# SyncLED.net
KiCad netlist of a schematic drawn in EAGLE
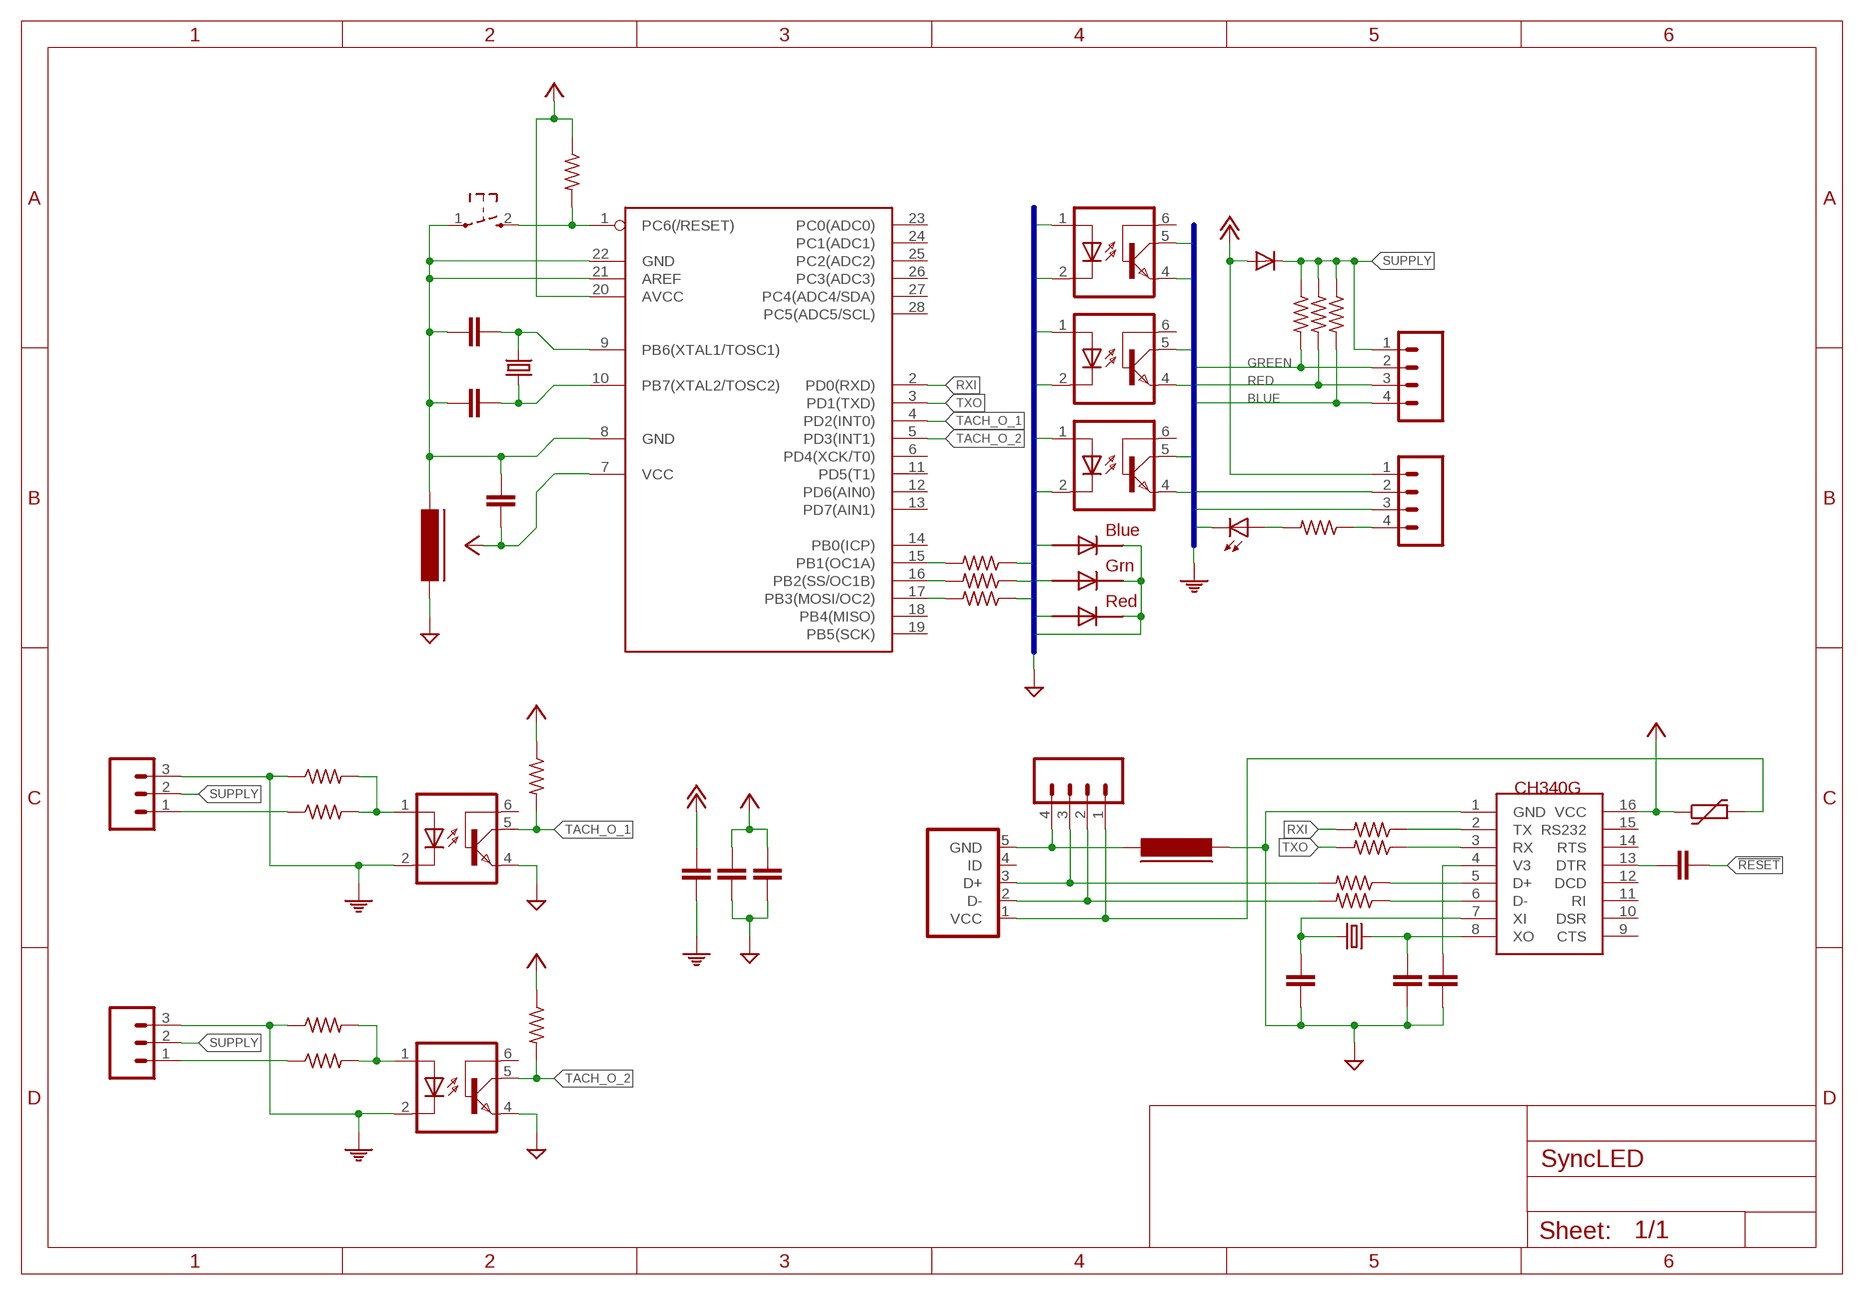
[diagram p0: schematic, sheet 1]

(export (version "E")
  (design (tool "Eeschema 10.0.6"))
  (components
    (comp (ref "!RES")
      (value "SMD")
      (footprint "eagle-import:SW_TACT_3X6")
      (libsource (lib "eagle-import") (part "SW_TACT_2P-3X6"))
    )
    (comp (ref "C1")
      (value "22pF")
      (footprint "eagle-import:C0805K")
      (libsource (lib "eagle-import") (part "C-EUC0805K"))
    )
    (comp (ref "C2")
      (value "22pF")
      (footprint "eagle-import:C0805K")
      (libsource (lib "eagle-import") (part "C-EUC0805K"))
    )
    (comp (ref "C3")
      (value "22pF")
      (footprint "eagle-import:C0805K")
      (libsource (lib "eagle-import") (part "C-EUC0805K"))
    )
    (comp (ref "C4")
      (value "22pF")
      (footprint "eagle-import:C0805K")
      (libsource (lib "eagle-import") (part "C-EUC0805K"))
    )
    (comp (ref "CAP_!DTR")
      (value "100nF")
      (footprint "eagle-import:C1206K")
      (libsource (lib "eagle-import") (part "C-EUC1206K"))
    )
    (comp (ref "CAP_BYPASS")
      (value "22pF")
      (footprint "eagle-import:C0805K")
      (libsource (lib "eagle-import") (part "C-EUC0805K"))
    )
    (comp (ref "CAP_DIGITAL_1")
      (value "1uF")
      (footprint "eagle-import:C1210K")
      (libsource (lib "eagle-import") (part "C-EUC1210K"))
    )
    (comp (ref "CAP_DIGITAL_2")
      (value "1uF")
      (footprint "eagle-import:C1210K")
      (libsource (lib "eagle-import") (part "C-EUC1210K"))
    )
    (comp (ref "CAP_LED")
      (value "1uF")
      (footprint "eagle-import:C1206K")
      (libsource (lib "eagle-import") (part "C-EUC1206K"))
    )
    (comp (ref "CAP_MCU")
      (value "10uF")
      (footprint "eagle-import:C1206K")
      (libsource (lib "eagle-import") (part "C-EUC1206K"))
    )
    (comp (ref "DIODE_LED")
      (value "1N4004")
      (footprint "eagle-import:DO41-10")
      (libsource (lib "eagle-import") (part "1N4004"))
    )
    (comp (ref "FAN_HEADER_1")
      (value "M03PTH")
      (footprint "eagle-import:1X03")
      (libsource (lib "eagle-import") (part "M03PTH"))
    )
    (comp (ref "FAN_HEADER_2")
      (value "M03PTH")
      (footprint "eagle-import:1X03")
      (libsource (lib "eagle-import") (part "M03PTH"))
    )
    (comp (ref "FERRITE_MCU")
      (value "UGND")
      (footprint "eagle-import:FB805")
      (libsource (lib "eagle-import") (part "FERRITE-0805"))
    )
    (comp (ref "FERRITE_USB")
      (value "UGND")
      (footprint "eagle-import:FB805")
      (libsource (lib "eagle-import") (part "FERRITE-0805"))
    )
    (comp (ref "INDICATOR")
      (value "RGBLED5050")
      (footprint "eagle-import:RGBLED5050")
      (libsource (lib "eagle-import") (part "RGBLED5050"))
    )
    (comp (ref "LED_OUTPUT")
      (value "M04PTH")
      (footprint "eagle-import:1X04")
      (libsource (lib "eagle-import") (part "SparkFun-Connectors_M04PTH"))
    )
    (comp (ref "MCU")
      (value "MEGA8-P")
      (footprint "eagle-import:DIL28-3")
      (libsource (lib "eagle-import") (part "MEGA8-P"))
    )
    (comp (ref "OPTO_BLUE")
      (value "4N35")
      (footprint "eagle-import:DIL06")
      (fields (field (name "MF") "FAIRCHILD SEMICONDUCTOR"))
      (libsource (lib "eagle-import") (part "4N35"))
    )
    (comp (ref "OPTO_GREEN")
      (value "4N35")
      (footprint "eagle-import:DIL06")
      (fields (field (name "MF") "FAIRCHILD SEMICONDUCTOR"))
      (libsource (lib "eagle-import") (part "4N35"))
    )
    (comp (ref "OPTO_RED")
      (value "4N35")
      (footprint "eagle-import:DIL06")
      (fields (field (name "MF") "FAIRCHILD SEMICONDUCTOR"))
      (libsource (lib "eagle-import") (part "4N35"))
    )
    (comp (ref "OPTO_TACH_1")
      (value "4N35")
      (footprint "eagle-import:DIL06")
      (fields (field (name "MF") "FAIRCHILD SEMICONDUCTOR"))
      (libsource (lib "eagle-import") (part "4N35"))
    )
    (comp (ref "OPTO_TACH_2")
      (value "4N35")
      (footprint "eagle-import:DIL06")
      (fields (field (name "MF") "FAIRCHILD SEMICONDUCTOR"))
      (libsource (lib "eagle-import") (part "4N35"))
    )
    (comp (ref "POWER_INDICATOR")
      (value "LEDCHIPLED_1206")
      (footprint "eagle-import:CHIPLED_1206")
      (libsource (lib "eagle-import") (part "LEDCHIPLED_1206"))
    )
    (comp (ref "PPTC")
      (value "500mA")
      (footprint "eagle-import:PTC0805")
      (libsource (lib "eagle-import") (part "FUSE_PTC-0805"))
    )
    (comp (ref "RES_BLUE")
      (value "10K")
      (footprint "eagle-import:0207_10")
      (libsource (lib "eagle-import") (part "R-US_0207/10"))
    )
    (comp (ref "RES_B_IN")
      (value "100E")
      (footprint "eagle-import:0207_12")
      (libsource (lib "eagle-import") (part "R-US_0207/12"))
    )
    (comp (ref "RES_D+")
      (value "100E")
      (footprint "eagle-import:M0805")
      (libsource (lib "eagle-import") (part "R-US_M0805"))
    )
    (comp (ref "RES_D-")
      (value "100E")
      (footprint "eagle-import:M0805")
      (libsource (lib "eagle-import") (part "R-US_M0805"))
    )
    (comp (ref "RES_GREEN")
      (value "10K")
      (footprint "eagle-import:0207_10")
      (libsource (lib "eagle-import") (part "R-US_0207/10"))
    )
    (comp (ref "RES_G_IN")
      (value "100E")
      (footprint "eagle-import:0207_12")
      (libsource (lib "eagle-import") (part "R-US_0207/12"))
    )
    (comp (ref "RES_LED")
      (value "10K")
      (footprint "eagle-import:M1206")
      (libsource (lib "eagle-import") (part "R-US_M1206"))
    )
    (comp (ref "RES_PULLUP")
      (value "10K")
      (footprint "eagle-import:0207_12")
      (libsource (lib "eagle-import") (part "R-US_0207/12"))
    )
    (comp (ref "RES_RED")
      (value "10K")
      (footprint "eagle-import:0207_10")
      (libsource (lib "eagle-import") (part "R-US_0207/10"))
    )
    (comp (ref "RES_RX")
      (value "100E")
      (footprint "eagle-import:0207_10")
      (libsource (lib "eagle-import") (part "R-US_0207/10"))
    )
    (comp (ref "RES_R_IN")
      (value "100E")
      (footprint "eagle-import:0207_12")
      (libsource (lib "eagle-import") (part "R-US_0207/12"))
    )
    (comp (ref "RES_TACH_1")
      (value "100E")
      (footprint "eagle-import:0207_10")
      (libsource (lib "eagle-import") (part "R-US_0207/10"))
    )
    (comp (ref "RES_TACH_2")
      (value "100E")
      (footprint "eagle-import:0207_10")
      (libsource (lib "eagle-import") (part "R-US_0207/10"))
    )
    (comp (ref "RES_TACH_PULLDOWN_1")
      (value "1K")
      (footprint "eagle-import:0207_10")
      (libsource (lib "eagle-import") (part "R-US_0207/10"))
    )
    (comp (ref "RES_TACH_PULLDOWN_2")
      (value "1K")
      (footprint "eagle-import:0207_10")
      (libsource (lib "eagle-import") (part "R-US_0207/10"))
    )
    (comp (ref "RES_TACH_PULLUP_1")
      (value "10K")
      (footprint "eagle-import:0207_10")
      (libsource (lib "eagle-import") (part "R-US_0207/10"))
    )
    (comp (ref "RES_TACH_PULLUP_2")
      (value "10K")
      (footprint "eagle-import:0207_10")
      (libsource (lib "eagle-import") (part "R-US_0207/10"))
    )
    (comp (ref "RES_TX")
      (value "100E")
      (footprint "eagle-import:0207_10")
      (libsource (lib "eagle-import") (part "R-US_0207/10"))
    )
    (comp (ref "SMPS_SUPPLY")
      (value "M04PTH")
      (footprint "eagle-import:1X04")
      (libsource (lib "eagle-import") (part "SparkFun-Connectors_M04PTH"))
    )
    (comp (ref "USB-RECEPTABLE")
      (value "USB-Micro")
      (footprint "eagle-import:FCI-10103594-0001LF")
      (libsource (lib "eagle-import") (part "USB-RECEPTABLE"))
    )
    (comp (ref "USB2UART")
      (value "CH340G")
      (footprint "eagle-import:SOIC16")
      (libsource (lib "eagle-import") (part "CH340G"))
    )
    (comp (ref "USB_PORT")
      (value "M04PTH")
      (footprint "eagle-import:1X04")
      (libsource (lib "eagle-import") (part "M04PTH"))
    )
    (comp (ref "XTAL_MCU")
      (value "CRYSTALHC49S")
      (footprint "eagle-import:HC49_S")
      (libsource (lib "eagle-import") (part "CRYSTALHC49S"))
    )
    (comp (ref "XTAL_USB")
      (value "CRYSTALHC49S")
      (footprint "eagle-import:HC49_S")
      (libsource (lib "eagle-import") (part "CRYSTALHC49S"))
    )
  )
  (nets
    (net (code "1") (name "+5V") (class "Default")
      (node (ref "CAP_DIGITAL_1") (pin "1") (pinfunction "1_1") (pintype "passive"))
      (node (ref "CAP_DIGITAL_2") (pin "1") (pinfunction "1_1") (pintype "passive"))
      (node (ref "CAP_MCU") (pin "1") (pinfunction "1_1") (pintype "passive"))
      (node (ref "MCU") (pin "20") (pinfunction "AVCC_20") (pintype "power_in"))
      (node (ref "MCU") (pin "7") (pinfunction "VCC_7") (pintype "power_in"))
      (node (ref "PPTC") (pin "1") (pinfunction "1_1") (pintype "passive"))
      (node (ref "RES_PULLUP") (pin "1") (pinfunction "1_1") (pintype "passive"))
      (node (ref "RES_TACH_PULLUP_1") (pin "1") (pinfunction "1_1") (pintype "passive"))
      (node (ref "RES_TACH_PULLUP_2") (pin "1") (pinfunction "1_1") (pintype "passive"))
      (node (ref "USB2UART") (pin "16") (pinfunction "VCC_16") (pintype "bidirectional"))
    )
    (net (code "2") (name "+12V") (class "Default")
      (node (ref "CAP_LED") (pin "1") (pinfunction "1_1") (pintype "passive"))
      (node (ref "DIODE_LED") (pin "A") (pinfunction "A_A") (pintype "passive"))
      (node (ref "SMPS_SUPPLY") (pin "1") (pinfunction "1_1") (pintype "passive"))
    )
    (net (code "3") (name "/BLUE") (class "Default")
      (node (ref "LED_OUTPUT") (pin "4") (pinfunction "4_4") (pintype "passive"))
      (node (ref "OPTO_BLUE") (pin "5") (pinfunction "COL_5") (pintype "passive"))
      (node (ref "RES_BLUE") (pin "2") (pinfunction "2_2") (pintype "passive"))
    )
    (net (code "4") (name "/B_OUT") (class "Default")
      (node (ref "INDICATOR") (pin "3") (pinfunction "BLUE_A_3") (pintype "bidirectional"))
      (node (ref "OPTO_BLUE") (pin "1") (pinfunction "A_1") (pintype "passive"))
      (node (ref "RES_B_IN") (pin "1") (pinfunction "1_1") (pintype "passive"))
    )
    (net (code "5") (name "/GREEN") (class "Default")
      (node (ref "LED_OUTPUT") (pin "2") (pinfunction "2_2") (pintype "passive"))
      (node (ref "OPTO_GREEN") (pin "5") (pinfunction "COL_5") (pintype "passive"))
      (node (ref "RES_RED") (pin "2") (pinfunction "2_2") (pintype "passive"))
    )
    (net (code "6") (name "/G_OUT") (class "Default")
      (node (ref "INDICATOR") (pin "1") (pinfunction "GREEN_A_1") (pintype "bidirectional"))
      (node (ref "OPTO_GREEN") (pin "1") (pinfunction "A_1") (pintype "passive"))
      (node (ref "RES_G_IN") (pin "1") (pinfunction "1_1") (pintype "passive"))
    )
    (net (code "7") (name "/RED") (class "Default")
      (node (ref "LED_OUTPUT") (pin "3") (pinfunction "3_3") (pintype "passive"))
      (node (ref "OPTO_RED") (pin "5") (pinfunction "COL_5") (pintype "passive"))
      (node (ref "RES_GREEN") (pin "2") (pinfunction "2_2") (pintype "passive"))
    )
    (net (code "8") (name "/R_OUT") (class "Default")
      (node (ref "INDICATOR") (pin "2") (pinfunction "RED_A_2") (pintype "bidirectional"))
      (node (ref "OPTO_RED") (pin "1") (pinfunction "A_1") (pintype "passive"))
      (node (ref "RES_R_IN") (pin "1") (pinfunction "1_1") (pintype "passive"))
    )
    (net (code "9") (name "/~{RESET}") (class "Default")
      (node (ref "!RES") (pin "2") (pinfunction "3_2") (pintype "passive"))
      (node (ref "CAP_!DTR") (pin "2") (pinfunction "2_2") (pintype "passive"))
      (node (ref "MCU") (pin "1") (pinfunction "PC6(/RESET)_1") (pintype "bidirectional"))
      (node (ref "RES_PULLUP") (pin "2") (pinfunction "2_2") (pintype "passive"))
    )
    (net (code "10") (name "DGND") (class "Default")
      (node (ref "C1") (pin "2") (pinfunction "2_2") (pintype "passive"))
      (node (ref "C2") (pin "2") (pinfunction "2_2") (pintype "passive"))
      (node (ref "CAP_BYPASS") (pin "2") (pinfunction "2_2") (pintype "passive"))
      (node (ref "CAP_DIGITAL_1") (pin "2") (pinfunction "2_2") (pintype "passive"))
      (node (ref "CAP_DIGITAL_2") (pin "2") (pinfunction "2_2") (pintype "passive"))
      (node (ref "FERRITE_MCU") (pin "1") (pinfunction "1_1") (pintype "passive"))
      (node (ref "FERRITE_USB") (pin "2") (pinfunction "2_2") (pintype "passive"))
      (node (ref "INDICATOR") (pin "4") (pinfunction "BLUE_C_4") (pintype "bidirectional"))
      (node (ref "INDICATOR") (pin "5") (pinfunction "RED_C_5") (pintype "bidirectional"))
      (node (ref "INDICATOR") (pin "6") (pinfunction "GREEN_C_6") (pintype "bidirectional"))
      (node (ref "OPTO_BLUE") (pin "2") (pinfunction "C_2") (pintype "passive"))
      (node (ref "OPTO_GREEN") (pin "2") (pinfunction "C_2") (pintype "passive"))
      (node (ref "OPTO_RED") (pin "2") (pinfunction "C_2") (pintype "passive"))
      (node (ref "OPTO_TACH_1") (pin "4") (pinfunction "EMI_4") (pintype "passive"))
      (node (ref "OPTO_TACH_2") (pin "4") (pinfunction "EMI_4") (pintype "passive"))
      (node (ref "USB2UART") (pin "1") (pinfunction "GND_1") (pintype "bidirectional"))
    )
    (net (code "11") (name "GROUND") (class "Default")
      (node (ref "CAP_LED") (pin "2") (pinfunction "2_2") (pintype "passive"))
      (node (ref "FAN_HEADER_1") (pin "3") (pinfunction "3_3") (pintype "passive"))
      (node (ref "FAN_HEADER_2") (pin "3") (pinfunction "3_3") (pintype "passive"))
      (node (ref "OPTO_BLUE") (pin "4") (pinfunction "EMI_4") (pintype "passive"))
      (node (ref "OPTO_GREEN") (pin "4") (pinfunction "EMI_4") (pintype "passive"))
      (node (ref "OPTO_RED") (pin "4") (pinfunction "EMI_4") (pintype "passive"))
      (node (ref "OPTO_TACH_1") (pin "2") (pinfunction "C_2") (pintype "passive"))
      (node (ref "OPTO_TACH_2") (pin "2") (pinfunction "C_2") (pintype "passive"))
      (node (ref "POWER_INDICATOR") (pin "C") (pinfunction "C_C") (pintype "passive"))
      (node (ref "RES_TACH_PULLDOWN_1") (pin "1") (pinfunction "1_1") (pintype "passive"))
      (node (ref "RES_TACH_PULLDOWN_2") (pin "1") (pinfunction "1_1") (pintype "passive"))
      (node (ref "SMPS_SUPPLY") (pin "2") (pinfunction "2_2") (pintype "passive"))
      (node (ref "SMPS_SUPPLY") (pin "3") (pinfunction "3_3") (pintype "passive"))
    )
    (net (code "12") (name "Net-(FAN_HEADER_1-Pad1)") (class "Default")
      (node (ref "FAN_HEADER_1") (pin "1") (pinfunction "1_1") (pintype "passive"))
      (node (ref "RES_TACH_1") (pin "1") (pinfunction "1_1") (pintype "passive"))
    )
    (net (code "13") (name "Net-(FAN_HEADER_2-Pad1)") (class "Default")
      (node (ref "FAN_HEADER_2") (pin "1") (pinfunction "1_1") (pintype "passive"))
      (node (ref "RES_TACH_2") (pin "1") (pinfunction "1_1") (pintype "passive"))
    )
    (net (code "14") (name "Net-(MCU-AREF)") (class "Default")
      (node (ref "!RES") (pin "1") (pinfunction "1_1") (pintype "passive"))
      (node (ref "C3") (pin "1") (pinfunction "1_1") (pintype "passive"))
      (node (ref "C4") (pin "1") (pinfunction "1_1") (pintype "passive"))
      (node (ref "CAP_MCU") (pin "2") (pinfunction "2_2") (pintype "passive"))
      (node (ref "FERRITE_MCU") (pin "2") (pinfunction "2_2") (pintype "passive"))
      (node (ref "MCU") (pin "21") (pinfunction "AREF_21") (pintype "passive"))
      (node (ref "MCU") (pin "22") (pinfunction "GND_22") (pintype "power_in"))
      (node (ref "MCU") (pin "8") (pinfunction "GND_8") (pintype "power_in"))
    )
    (net (code "15") (name "Net-(MCU-PB1(OC1A))") (class "Default")
      (node (ref "MCU") (pin "15") (pinfunction "PB1(OC1A)_15") (pintype "bidirectional"))
      (node (ref "RES_R_IN") (pin "2") (pinfunction "2_2") (pintype "passive"))
    )
    (net (code "16") (name "Net-(MCU-PB2(SS{slash}OC1B))") (class "Default")
      (node (ref "MCU") (pin "16") (pinfunction "PB2(SS/OC1B)_16") (pintype "bidirectional"))
      (node (ref "RES_G_IN") (pin "2") (pinfunction "2_2") (pintype "passive"))
    )
    (net (code "17") (name "Net-(MCU-PB3(MOSI{slash}OC2))") (class "Default")
      (node (ref "MCU") (pin "17") (pinfunction "PB3(MOSI/OC2)_17") (pintype "bidirectional"))
      (node (ref "RES_B_IN") (pin "2") (pinfunction "2_2") (pintype "passive"))
    )
    (net (code "18") (name "Net-(MCU-PB6(XTAL1{slash}TOSC1))") (class "Default")
      (node (ref "C3") (pin "2") (pinfunction "2_2") (pintype "passive"))
      (node (ref "MCU") (pin "9") (pinfunction "PB6(XTAL1/TOSC1)_9") (pintype "bidirectional"))
      (node (ref "XTAL_MCU") (pin "2") (pinfunction "2_2") (pintype "passive"))
    )
    (net (code "19") (name "Net-(MCU-PB7(XTAL2{slash}TOSC2))") (class "Default")
      (node (ref "C4") (pin "2") (pinfunction "2_2") (pintype "passive"))
      (node (ref "MCU") (pin "10") (pinfunction "PB7(XTAL2/TOSC2)_10") (pintype "bidirectional"))
      (node (ref "XTAL_MCU") (pin "1") (pinfunction "1_1") (pintype "passive"))
    )
    (net (code "20") (name "Net-(OPTO_TACH_1-A)") (class "Default")
      (node (ref "OPTO_TACH_1") (pin "1") (pinfunction "A_1") (pintype "passive"))
      (node (ref "RES_TACH_1") (pin "2") (pinfunction "2_2") (pintype "passive"))
      (node (ref "RES_TACH_PULLDOWN_1") (pin "2") (pinfunction "2_2") (pintype "passive"))
    )
    (net (code "21") (name "Net-(OPTO_TACH_2-A)") (class "Default")
      (node (ref "OPTO_TACH_2") (pin "1") (pinfunction "A_1") (pintype "passive"))
      (node (ref "RES_TACH_2") (pin "2") (pinfunction "2_2") (pintype "passive"))
      (node (ref "RES_TACH_PULLDOWN_2") (pin "2") (pinfunction "2_2") (pintype "passive"))
    )
    (net (code "22") (name "Net-(POWER_INDICATOR-PadA)") (class "Default")
      (node (ref "POWER_INDICATOR") (pin "A") (pinfunction "A_A") (pintype "passive"))
      (node (ref "RES_LED") (pin "2") (pinfunction "2_2") (pintype "passive"))
    )
    (net (code "23") (name "Net-(RES_LED-Pad1)") (class "Default")
      (node (ref "RES_LED") (pin "1") (pinfunction "1_1") (pintype "passive"))
      (node (ref "SMPS_SUPPLY") (pin "4") (pinfunction "4_4") (pintype "passive"))
    )
    (net (code "24") (name "Net-(USB-RECEPTABLE-D+)") (class "Default")
      (node (ref "RES_D+") (pin "2") (pinfunction "2_2") (pintype "passive"))
      (node (ref "USB-RECEPTABLE") (pin "3") (pinfunction "D+_3") (pintype "bidirectional"))
      (node (ref "USB_PORT") (pin "3") (pinfunction "3_3") (pintype "passive"))
    )
    (net (code "25") (name "Net-(USB-RECEPTABLE-D-)") (class "Default")
      (node (ref "RES_D-") (pin "2") (pinfunction "2_2") (pintype "passive"))
      (node (ref "USB-RECEPTABLE") (pin "2") (pinfunction "D-_2") (pintype "bidirectional"))
      (node (ref "USB_PORT") (pin "2") (pinfunction "2_2") (pintype "passive"))
    )
    (net (code "26") (name "Net-(USB-RECEPTABLE-GND)") (class "Default")
      (node (ref "FERRITE_USB") (pin "1") (pinfunction "1_1") (pintype "passive"))
      (node (ref "USB-RECEPTABLE") (pin "5") (pinfunction "GND_5") (pintype "bidirectional"))
      (node (ref "USB_PORT") (pin "4") (pinfunction "4_4") (pintype "passive"))
    )
    (net (code "27") (name "Net-(USB-RECEPTABLE-VCC)") (class "Default")
      (node (ref "PPTC") (pin "2") (pinfunction "2_2") (pintype "passive"))
      (node (ref "USB-RECEPTABLE") (pin "1") (pinfunction "VCC_1") (pintype "bidirectional"))
      (node (ref "USB_PORT") (pin "1") (pinfunction "1_1") (pintype "passive"))
    )
    (net (code "28") (name "Net-(USB2UART-D+)") (class "Default")
      (node (ref "RES_D+") (pin "1") (pinfunction "1_1") (pintype "passive"))
      (node (ref "USB2UART") (pin "5") (pinfunction "D+_5") (pintype "bidirectional"))
    )
    (net (code "29") (name "Net-(USB2UART-D-)") (class "Default")
      (node (ref "RES_D-") (pin "1") (pinfunction "1_1") (pintype "passive"))
      (node (ref "USB2UART") (pin "6") (pinfunction "D-_6") (pintype "bidirectional"))
    )
    (net (code "30") (name "Net-(USB2UART-DTR)") (class "Default")
      (node (ref "CAP_!DTR") (pin "1") (pinfunction "1_1") (pintype "passive"))
      (node (ref "USB2UART") (pin "13") (pinfunction "DTR_13") (pintype "bidirectional"))
    )
    (net (code "31") (name "Net-(USB2UART-RX)") (class "Default")
      (node (ref "RES_RX") (pin "1") (pinfunction "1_1") (pintype "passive"))
      (node (ref "USB2UART") (pin "3") (pinfunction "RX_3") (pintype "bidirectional"))
    )
    (net (code "32") (name "Net-(USB2UART-TX)") (class "Default")
      (node (ref "RES_TX") (pin "1") (pinfunction "1_1") (pintype "passive"))
      (node (ref "USB2UART") (pin "2") (pinfunction "TX_2") (pintype "bidirectional"))
    )
    (net (code "33") (name "Net-(USB2UART-V3)") (class "Default")
      (node (ref "CAP_BYPASS") (pin "1") (pinfunction "1_1") (pintype "passive"))
      (node (ref "USB2UART") (pin "4") (pinfunction "V3_4") (pintype "bidirectional"))
    )
    (net (code "34") (name "Net-(USB2UART-XI)") (class "Default")
      (node (ref "C2") (pin "1") (pinfunction "1_1") (pintype "passive"))
      (node (ref "USB2UART") (pin "7") (pinfunction "XI_7") (pintype "bidirectional"))
      (node (ref "XTAL_USB") (pin "1") (pinfunction "1_1") (pintype "passive"))
    )
    (net (code "35") (name "Net-(USB2UART-XO)") (class "Default")
      (node (ref "C1") (pin "1") (pinfunction "1_1") (pintype "passive"))
      (node (ref "USB2UART") (pin "8") (pinfunction "XO_8") (pintype "bidirectional"))
      (node (ref "XTAL_USB") (pin "2") (pinfunction "2_2") (pintype "passive"))
    )
    (net (code "36") (name "RXI") (class "Default")
      (node (ref "MCU") (pin "2") (pinfunction "PD0(RXD)_2") (pintype "bidirectional"))
      (node (ref "RES_TX") (pin "2") (pinfunction "2_2") (pintype "passive"))
    )
    (net (code "37") (name "SUPPLY") (class "Default")
      (node (ref "DIODE_LED") (pin "C") (pinfunction "C_C") (pintype "passive"))
      (node (ref "FAN_HEADER_1") (pin "2") (pinfunction "2_2") (pintype "passive"))
      (node (ref "FAN_HEADER_2") (pin "2") (pinfunction "2_2") (pintype "passive"))
      (node (ref "LED_OUTPUT") (pin "1") (pinfunction "1_1") (pintype "passive"))
      (node (ref "RES_BLUE") (pin "1") (pinfunction "1_1") (pintype "passive"))
      (node (ref "RES_GREEN") (pin "1") (pinfunction "1_1") (pintype "passive"))
      (node (ref "RES_RED") (pin "1") (pinfunction "1_1") (pintype "passive"))
    )
    (net (code "38") (name "TACH_O_1") (class "Default")
      (node (ref "MCU") (pin "4") (pinfunction "PD2(INT0)_4") (pintype "bidirectional"))
      (node (ref "OPTO_TACH_1") (pin "5") (pinfunction "COL_5") (pintype "passive"))
      (node (ref "RES_TACH_PULLUP_1") (pin "2") (pinfunction "2_2") (pintype "passive"))
    )
    (net (code "39") (name "TACH_O_2") (class "Default")
      (node (ref "MCU") (pin "5") (pinfunction "PD3(INT1)_5") (pintype "bidirectional"))
      (node (ref "OPTO_TACH_2") (pin "5") (pinfunction "COL_5") (pintype "passive"))
      (node (ref "RES_TACH_PULLUP_2") (pin "2") (pinfunction "2_2") (pintype "passive"))
    )
    (net (code "40") (name "TXO") (class "Default")
      (node (ref "MCU") (pin "3") (pinfunction "PD1(TXD)_3") (pintype "bidirectional"))
      (node (ref "RES_RX") (pin "2") (pinfunction "2_2") (pintype "passive"))
    )
    (net (code "41") (name "unconnected-(MCU-PB0(ICP)-Pad14)") (class "Default")
      (node (ref "MCU") (pin "14") (pinfunction "PB0(ICP)_14") (pintype "bidirectional"))
    )
    (net (code "42") (name "unconnected-(MCU-PB4(MISO)-Pad18)") (class "Default")
      (node (ref "MCU") (pin "18") (pinfunction "PB4(MISO)_18") (pintype "bidirectional"))
    )
    (net (code "43") (name "unconnected-(MCU-PB5(SCK)-Pad19)") (class "Default")
      (node (ref "MCU") (pin "19") (pinfunction "PB5(SCK)_19") (pintype "bidirectional"))
    )
    (net (code "44") (name "unconnected-(MCU-PC0(ADC0)-Pad23)") (class "Default")
      (node (ref "MCU") (pin "23") (pinfunction "PC0(ADC0)_23") (pintype "bidirectional"))
    )
    (net (code "45") (name "unconnected-(MCU-PC1(ADC1)-Pad24)") (class "Default")
      (node (ref "MCU") (pin "24") (pinfunction "PC1(ADC1)_24") (pintype "bidirectional"))
    )
    (net (code "46") (name "unconnected-(MCU-PC2(ADC2)-Pad25)") (class "Default")
      (node (ref "MCU") (pin "25") (pinfunction "PC2(ADC2)_25") (pintype "bidirectional"))
    )
    (net (code "47") (name "unconnected-(MCU-PC3(ADC3)-Pad26)") (class "Default")
      (node (ref "MCU") (pin "26") (pinfunction "PC3(ADC3)_26") (pintype "bidirectional"))
    )
    (net (code "48") (name "unconnected-(MCU-PC4(ADC4{slash}SDA)-Pad27)") (class "Default")
      (node (ref "MCU") (pin "27") (pinfunction "PC4(ADC4/SDA)_27") (pintype "bidirectional"))
    )
    (net (code "49") (name "unconnected-(MCU-PC5(ADC5{slash}SCL)-Pad28)") (class "Default")
      (node (ref "MCU") (pin "28") (pinfunction "PC5(ADC5/SCL)_28") (pintype "bidirectional"))
    )
    (net (code "50") (name "unconnected-(MCU-PD4(XCK{slash}T0)-Pad6)") (class "Default")
      (node (ref "MCU") (pin "6") (pinfunction "PD4(XCK/T0)_6") (pintype "bidirectional"))
    )
    (net (code "51") (name "unconnected-(MCU-PD5(T1)-Pad11)") (class "Default")
      (node (ref "MCU") (pin "11") (pinfunction "PD5(T1)_11") (pintype "bidirectional"))
    )
    (net (code "52") (name "unconnected-(MCU-PD6(AIN0)-Pad12)") (class "Default")
      (node (ref "MCU") (pin "12") (pinfunction "PD6(AIN0)_12") (pintype "bidirectional"))
    )
    (net (code "53") (name "unconnected-(MCU-PD7(AIN1)-Pad13)") (class "Default")
      (node (ref "MCU") (pin "13") (pinfunction "PD7(AIN1)_13") (pintype "bidirectional"))
    )
    (net (code "54") (name "unconnected-(OPTO_BLUE-BAS-Pad6)") (class "Default")
      (node (ref "OPTO_BLUE") (pin "6") (pinfunction "BAS_6") (pintype "passive"))
    )
    (net (code "55") (name "unconnected-(OPTO_GREEN-BAS-Pad6)") (class "Default")
      (node (ref "OPTO_GREEN") (pin "6") (pinfunction "BAS_6") (pintype "passive"))
    )
    (net (code "56") (name "unconnected-(OPTO_RED-BAS-Pad6)") (class "Default")
      (node (ref "OPTO_RED") (pin "6") (pinfunction "BAS_6") (pintype "passive"))
    )
    (net (code "57") (name "unconnected-(OPTO_TACH_1-BAS-Pad6)") (class "Default")
      (node (ref "OPTO_TACH_1") (pin "6") (pinfunction "BAS_6") (pintype "passive"))
    )
    (net (code "58") (name "unconnected-(OPTO_TACH_2-BAS-Pad6)") (class "Default")
      (node (ref "OPTO_TACH_2") (pin "6") (pinfunction "BAS_6") (pintype "passive"))
    )
    (net (code "59") (name "unconnected-(USB-RECEPTABLE-ID-Pad4)") (class "Default")
      (node (ref "USB-RECEPTABLE") (pin "4") (pinfunction "ID_4") (pintype "bidirectional"))
    )
    (net (code "60") (name "unconnected-(USB2UART-CTS-Pad9)") (class "Default")
      (node (ref "USB2UART") (pin "9") (pinfunction "CTS_9") (pintype "bidirectional"))
    )
    (net (code "61") (name "unconnected-(USB2UART-DCD-Pad12)") (class "Default")
      (node (ref "USB2UART") (pin "12") (pinfunction "DCD_12") (pintype "bidirectional"))
    )
    (net (code "62") (name "unconnected-(USB2UART-DSR-Pad10)") (class "Default")
      (node (ref "USB2UART") (pin "10") (pinfunction "DSR_10") (pintype "bidirectional"))
    )
    (net (code "63") (name "unconnected-(USB2UART-RI-Pad11)") (class "Default")
      (node (ref "USB2UART") (pin "11") (pinfunction "RI_11") (pintype "bidirectional"))
    )
    (net (code "64") (name "unconnected-(USB2UART-RS232-Pad15)") (class "Default")
      (node (ref "USB2UART") (pin "15") (pinfunction "RS232_15") (pintype "bidirectional"))
    )
    (net (code "65") (name "unconnected-(USB2UART-RTS-Pad14)") (class "Default")
      (node (ref "USB2UART") (pin "14") (pinfunction "RTS_14") (pintype "bidirectional"))
    )
  )
)
